# LM317TC_V2.net
KiCad netlist of a schematic drawn in EAGLE
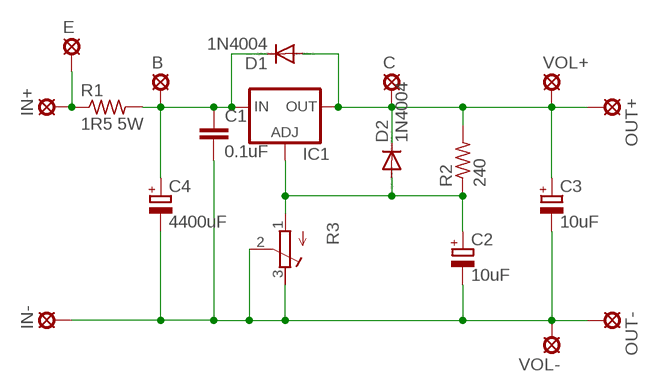
[diagram p0: schematic, sheet 1]

(export (version "E")
  (design (tool "Eeschema 10.0.6"))
  (components
    (comp (ref "B")
      (value "LSP10")
      (footprint "eagle-import:LSP10")
      (libsource (lib "eagle-import") (part "LSP10"))
    )
    (comp (ref "C")
      (value "LSP10")
      (footprint "eagle-import:LSP10")
      (libsource (lib "eagle-import") (part "LSP10"))
    )
    (comp (ref "C1")
      (value "0.1uF")
      (footprint "eagle-import:C050-025X075")
      (libsource (lib "eagle-import") (part "C-EU050-025X075"))
    )
    (comp (ref "C2")
      (value "10uF")
      (footprint "eagle-import:E2,5-7")
      (libsource (lib "eagle-import") (part "CPOL-EUE2.5-7"))
    )
    (comp (ref "C3")
      (value "10uF")
      (footprint "eagle-import:E2,5-7")
      (libsource (lib "eagle-import") (part "CPOL-EUE2.5-7"))
    )
    (comp (ref "C4")
      (value "4400uF")
      (footprint "eagle-import:E2,5-7")
      (libsource (lib "eagle-import") (part "CPOL-EUE2.5-7"))
    )
    (comp (ref "D1")
      (value "1N4004")
      (footprint "eagle-import:DO41-10")
      (libsource (lib "eagle-import") (part "1N4004"))
    )
    (comp (ref "D2")
      (value "1N4004")
      (footprint "eagle-import:DO41-10")
      (libsource (lib "eagle-import") (part "1N4004"))
    )
    (comp (ref "E")
      (value "LSP10")
      (footprint "eagle-import:LSP10")
      (libsource (lib "eagle-import") (part "LSP10"))
    )
    (comp (ref "IC1")
      (value "LM317TS")
      (footprint "eagle-import:317TS")
      (libsource (lib "eagle-import") (part "LM317TS"))
    )
    (comp (ref "IN+")
      (value "LSP10")
      (footprint "eagle-import:LSP10")
      (libsource (lib "eagle-import") (part "LSP10"))
    )
    (comp (ref "IN-")
      (value "LSP10")
      (footprint "eagle-import:LSP10")
      (libsource (lib "eagle-import") (part "LSP10"))
    )
    (comp (ref "OUT+")
      (value "LSP10")
      (footprint "eagle-import:LSP10")
      (libsource (lib "eagle-import") (part "LSP10"))
    )
    (comp (ref "OUT-")
      (value "LSP10")
      (footprint "eagle-import:LSP10")
      (libsource (lib "eagle-import") (part "LSP10"))
    )
    (comp (ref "R1")
      (value "1R5 5W")
      (footprint "eagle-import:0207_15")
      (libsource (lib "eagle-import") (part "R-US_0207/15"))
    )
    (comp (ref "R2")
      (value "240")
      (footprint "eagle-import:0207_10")
      (libsource (lib "eagle-import") (part "R-US_0207/10"))
    )
    (comp (ref "R3")
      (value "R-TRIMM3339P")
      (footprint "eagle-import:RTRIM3339P")
      (libsource (lib "eagle-import") (part "R-TRIMM3339P"))
    )
    (comp (ref "VOL+")
      (value "LSP10")
      (footprint "eagle-import:LSP10")
      (libsource (lib "eagle-import") (part "LSP10"))
    )
    (comp (ref "VOL-")
      (value "LSP10")
      (footprint "eagle-import:LSP10")
      (libsource (lib "eagle-import") (part "LSP10"))
    )
  )
  (nets
    (net (code "1") (name "Net-(E-PadMP)") (class "Default")
      (node (ref "E") (pin "MP") (pinfunction "MP_MP") (pintype "passive"))
      (node (ref "IN+") (pin "MP") (pinfunction "MP_MP") (pintype "passive"))
      (node (ref "R1") (pin "1") (pinfunction "1_1") (pintype "passive"))
    )
    (net (code "2") (name "Net-(IC1-ADJ)") (class "Default")
      (node (ref "C2") (pin "+") (pinfunction "+_+") (pintype "passive"))
      (node (ref "D2") (pin "A") (pinfunction "A_A") (pintype "passive"))
      (node (ref "IC1") (pin "1") (pinfunction "ADJ_1") (pintype "input"))
      (node (ref "R2") (pin "1") (pinfunction "1_1") (pintype "passive"))
      (node (ref "R3") (pin "1") (pinfunction "A_1") (pintype "passive"))
    )
    (net (code "3") (name "Net-(IC1-IN)") (class "Default")
      (node (ref "B") (pin "MP") (pinfunction "MP_MP") (pintype "passive"))
      (node (ref "C1") (pin "1") (pinfunction "1_1") (pintype "passive"))
      (node (ref "C4") (pin "+") (pinfunction "+_+") (pintype "passive"))
      (node (ref "D1") (pin "C") (pinfunction "C_C") (pintype "passive"))
      (node (ref "IC1") (pin "3") (pinfunction "IN_3") (pintype "input"))
      (node (ref "R1") (pin "2") (pinfunction "2_2") (pintype "passive"))
    )
    (net (code "4") (name "Net-(IC1-OUT)") (class "Default")
      (node (ref "C") (pin "MP") (pinfunction "MP_MP") (pintype "passive"))
      (node (ref "C3") (pin "+") (pinfunction "+_+") (pintype "passive"))
      (node (ref "D1") (pin "A") (pinfunction "A_A") (pintype "passive"))
      (node (ref "D2") (pin "C") (pinfunction "C_C") (pintype "passive"))
      (node (ref "IC1") (pin "2") (pinfunction "OUT_2") (pintype "passive"))
      (node (ref "OUT+") (pin "MP") (pinfunction "MP_MP") (pintype "passive"))
      (node (ref "R2") (pin "2") (pinfunction "2_2") (pintype "passive"))
      (node (ref "VOL+") (pin "MP") (pinfunction "MP_MP") (pintype "passive"))
    )
    (net (code "5") (name "Net-(R3-E)") (class "Default")
      (node (ref "C1") (pin "2") (pinfunction "2_2") (pintype "passive"))
      (node (ref "C2") (pin "-") (pinfunction "-_-") (pintype "passive"))
      (node (ref "C3") (pin "-") (pinfunction "-_-") (pintype "passive"))
      (node (ref "C4") (pin "-") (pinfunction "-_-") (pintype "passive"))
      (node (ref "IN-") (pin "MP") (pinfunction "MP_MP") (pintype "passive"))
      (node (ref "OUT-") (pin "MP") (pinfunction "MP_MP") (pintype "passive"))
      (node (ref "R3") (pin "2") (pinfunction "S_2") (pintype "passive"))
      (node (ref "R3") (pin "3") (pinfunction "E_3") (pintype "passive"))
      (node (ref "VOL-") (pin "MP") (pinfunction "MP_MP") (pintype "passive"))
    )
  )
)
